# Transceiver_1_0.net
KiCad netlist of a schematic drawn in EAGLE
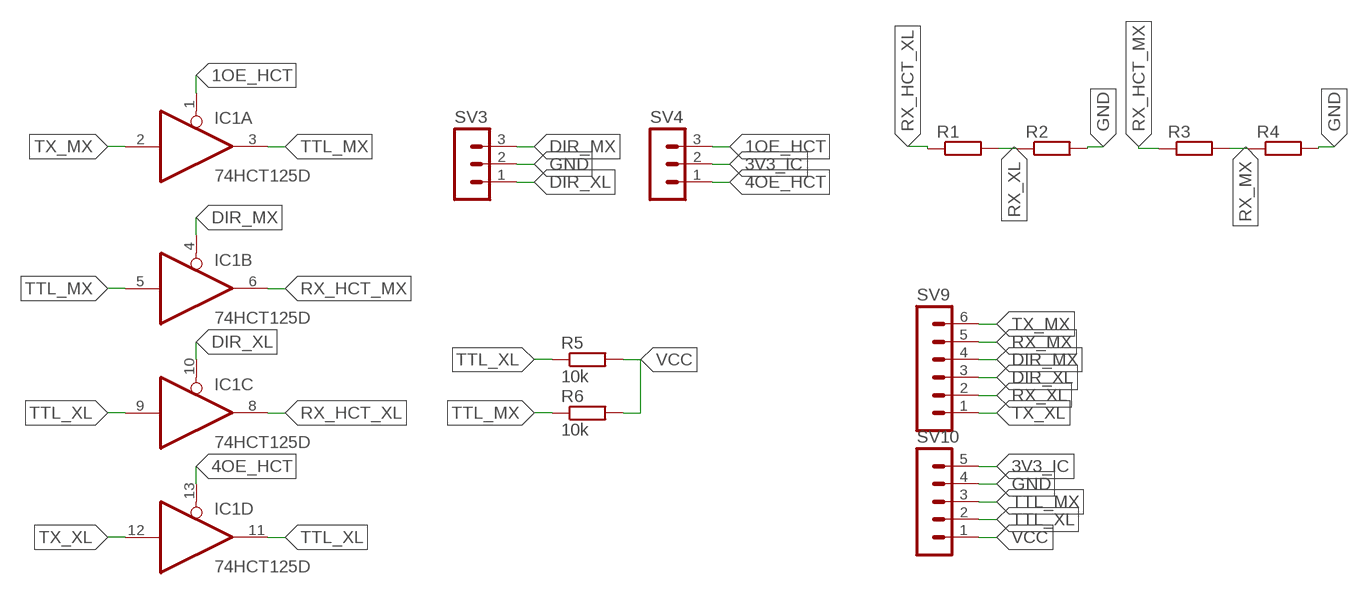
[diagram p0: schematic, sheet 1]

(export (version "E")
  (design (tool "Eeschema 10.0.6"))
  (components
    (comp (ref "IC1")
      (value "74HCT125D")
      (footprint "eagle-import:SO14")
      (libsource (lib "eagle-import") (part "74125DHCT"))
    )
    (comp (ref "R1")
      (value "R-EU_R1206")
      (footprint "eagle-import:R1206")
      (libsource (lib "eagle-import") (part "R-EU_R1206"))
    )
    (comp (ref "R2")
      (value "R-EU_R1206")
      (footprint "eagle-import:R1206")
      (libsource (lib "eagle-import") (part "R-EU_R1206"))
    )
    (comp (ref "R3")
      (value "R-EU_R1206")
      (footprint "eagle-import:R1206")
      (libsource (lib "eagle-import") (part "R-EU_R1206"))
    )
    (comp (ref "R4")
      (value "R-EU_R1206")
      (footprint "eagle-import:R1206")
      (libsource (lib "eagle-import") (part "R-EU_R1206"))
    )
    (comp (ref "R5")
      (value "10k")
      (footprint "eagle-import:R1206")
      (libsource (lib "eagle-import") (part "R-EU_R1206"))
    )
    (comp (ref "R6")
      (value "10k")
      (footprint "eagle-import:R1206")
      (libsource (lib "eagle-import") (part "R-EU_R1206"))
    )
    (comp (ref "SV3")
      (value "MA03-1")
      (footprint "eagle-import:MA03-1")
      (libsource (lib "eagle-import") (part "MA03-1"))
    )
    (comp (ref "SV4")
      (value "MA03-1")
      (footprint "eagle-import:MA03-1")
      (libsource (lib "eagle-import") (part "MA03-1"))
    )
    (comp (ref "SV9")
      (value "MA06-1")
      (footprint "eagle-import:MA06-1")
      (libsource (lib "eagle-import") (part "MA06-1"))
    )
    (comp (ref "SV10")
      (value "MA05-1")
      (footprint "eagle-import:MA05-1")
      (libsource (lib "eagle-import") (part "MA05-1"))
    )
  )
  (nets
    (net (code "1") (name "1OE_HCT") (class "Default")
      (node (ref "IC1") (pin "1") (pinfunction "OE_1") (pintype "input"))
      (node (ref "SV4") (pin "3") (pinfunction "3_3") (pintype "passive"))
    )
    (net (code "2") (name "3V3_IC") (class "Default")
      (node (ref "SV10") (pin "5") (pinfunction "5_5") (pintype "passive"))
      (node (ref "SV4") (pin "2") (pinfunction "2_2") (pintype "passive"))
    )
    (net (code "3") (name "4OE_HCT") (class "Default")
      (node (ref "IC1") (pin "13") (pinfunction "OE_13") (pintype "input"))
      (node (ref "SV4") (pin "1") (pinfunction "1_1") (pintype "passive"))
    )
    (net (code "4") (name "DIR_MX") (class "Default")
      (node (ref "IC1") (pin "4") (pinfunction "OE_4") (pintype "input"))
      (node (ref "SV3") (pin "3") (pinfunction "3_3") (pintype "passive"))
      (node (ref "SV9") (pin "4") (pinfunction "4_4") (pintype "passive"))
    )
    (net (code "5") (name "DIR_XL") (class "Default")
      (node (ref "IC1") (pin "10") (pinfunction "OE_10") (pintype "input"))
      (node (ref "SV3") (pin "1") (pinfunction "1_1") (pintype "passive"))
      (node (ref "SV9") (pin "3") (pinfunction "3_3") (pintype "passive"))
    )
    (net (code "6") (name "GND") (class "Default")
      (node (ref "R2") (pin "2") (pinfunction "2_2") (pintype "passive"))
      (node (ref "R4") (pin "2") (pinfunction "2_2") (pintype "passive"))
      (node (ref "SV10") (pin "4") (pinfunction "4_4") (pintype "passive"))
      (node (ref "SV3") (pin "2") (pinfunction "2_2") (pintype "passive"))
    )
    (net (code "7") (name "RX_HCT_MX") (class "Default")
      (node (ref "IC1") (pin "6") (pinfunction "O_6") (pintype "tri_state"))
      (node (ref "R3") (pin "1") (pinfunction "1_1") (pintype "passive"))
    )
    (net (code "8") (name "RX_HCT_XL") (class "Default")
      (node (ref "IC1") (pin "8") (pinfunction "O_8") (pintype "tri_state"))
      (node (ref "R1") (pin "1") (pinfunction "1_1") (pintype "passive"))
    )
    (net (code "9") (name "RX_MX") (class "Default")
      (node (ref "R3") (pin "2") (pinfunction "2_2") (pintype "passive"))
      (node (ref "R4") (pin "1") (pinfunction "1_1") (pintype "passive"))
      (node (ref "SV9") (pin "5") (pinfunction "5_5") (pintype "passive"))
    )
    (net (code "10") (name "RX_XL") (class "Default")
      (node (ref "R1") (pin "2") (pinfunction "2_2") (pintype "passive"))
      (node (ref "R2") (pin "1") (pinfunction "1_1") (pintype "passive"))
      (node (ref "SV9") (pin "2") (pinfunction "2_2") (pintype "passive"))
    )
    (net (code "11") (name "TTL_MX") (class "Default")
      (node (ref "IC1") (pin "3") (pinfunction "O_3") (pintype "tri_state"))
      (node (ref "IC1") (pin "5") (pinfunction "I_5") (pintype "input"))
      (node (ref "R6") (pin "1") (pinfunction "1_1") (pintype "passive"))
      (node (ref "SV10") (pin "3") (pinfunction "3_3") (pintype "passive"))
    )
    (net (code "12") (name "TTL_XL") (class "Default")
      (node (ref "IC1") (pin "11") (pinfunction "O_11") (pintype "tri_state"))
      (node (ref "IC1") (pin "9") (pinfunction "I_9") (pintype "input"))
      (node (ref "R5") (pin "1") (pinfunction "1_1") (pintype "passive"))
      (node (ref "SV10") (pin "2") (pinfunction "2_2") (pintype "passive"))
    )
    (net (code "13") (name "TX_MX") (class "Default")
      (node (ref "IC1") (pin "2") (pinfunction "I_2") (pintype "input"))
      (node (ref "SV9") (pin "6") (pinfunction "6_6") (pintype "passive"))
    )
    (net (code "14") (name "TX_XL") (class "Default")
      (node (ref "IC1") (pin "12") (pinfunction "I_12") (pintype "input"))
      (node (ref "SV9") (pin "1") (pinfunction "1_1") (pintype "passive"))
    )
    (net (code "15") (name "VCC") (class "Default")
      (node (ref "R5") (pin "2") (pinfunction "2_2") (pintype "passive"))
      (node (ref "R6") (pin "2") (pinfunction "2_2") (pintype "passive"))
      (node (ref "SV10") (pin "1") (pinfunction "1_1") (pintype "passive"))
    )
  )
)
